# Wireless.net
KiCad netlist of a schematic drawn in Altium Designer
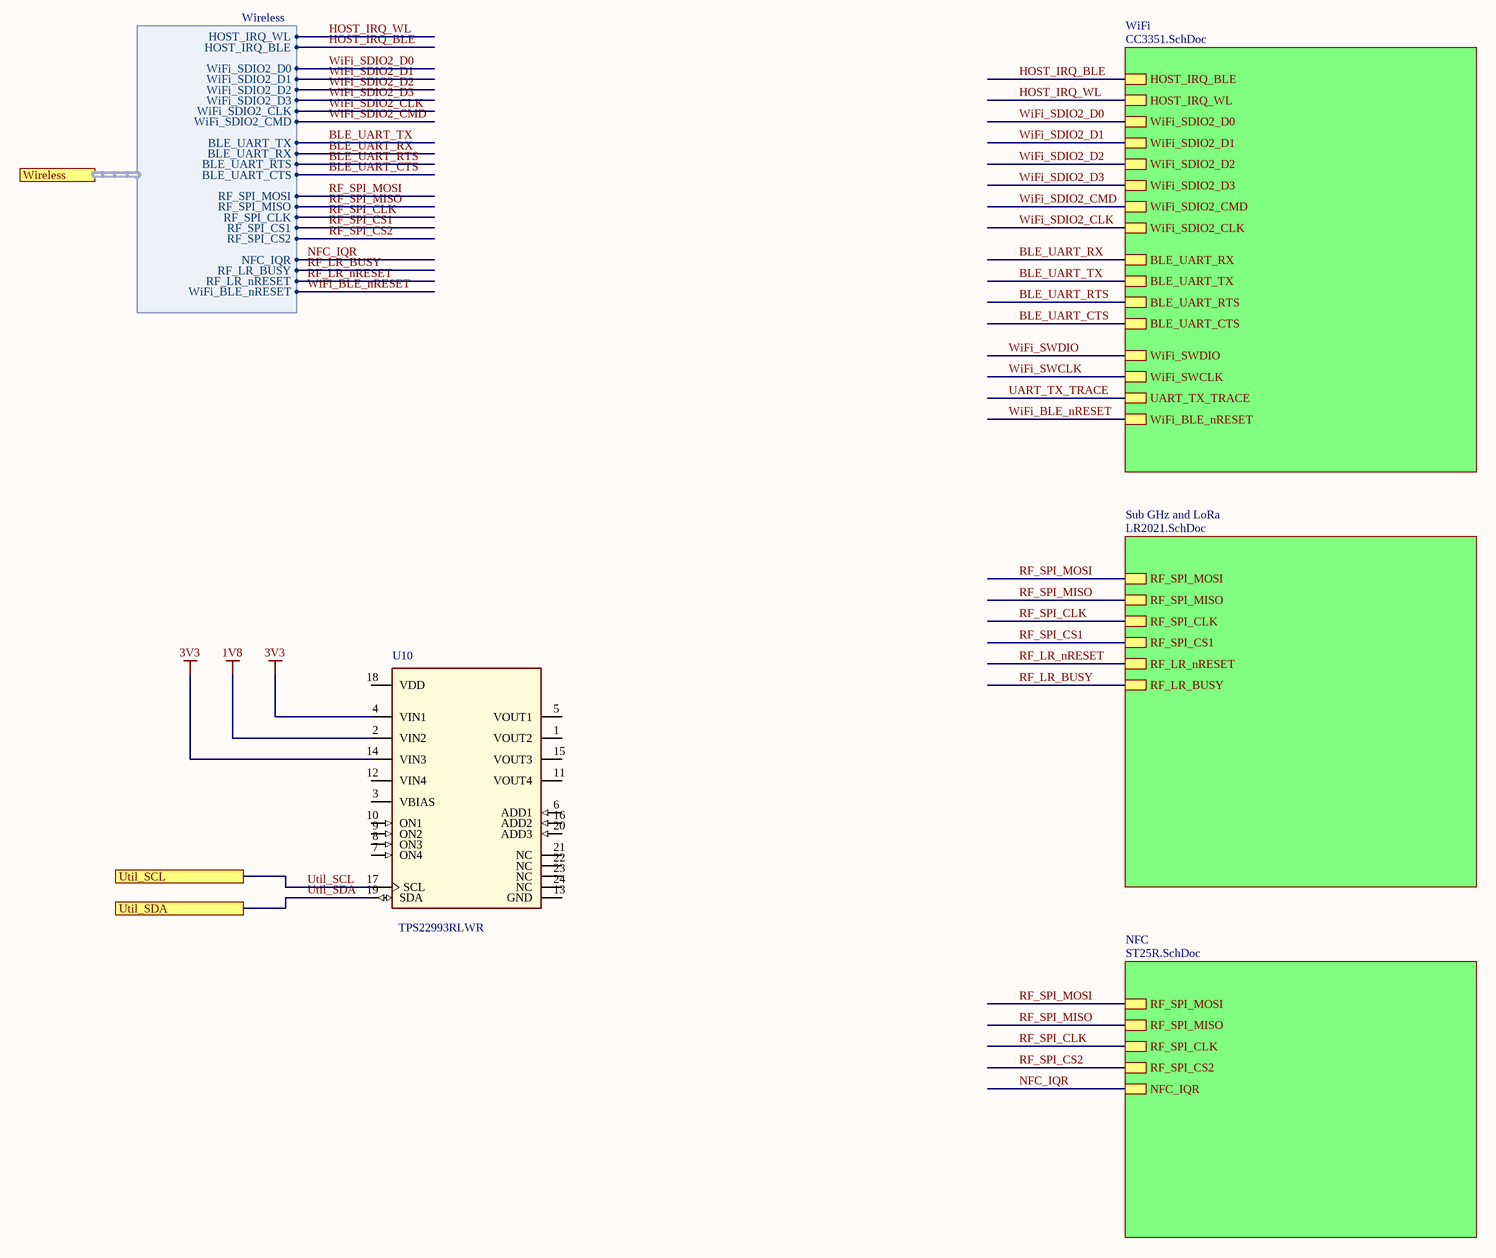
[diagram p0: Wireless.SchDoc]

(export (version "E")
  (design (tool "Eeschema 10.0.6"))
  (components
    (comp (ref "U10")
      (value "TPS22993RLWR")
      (footprint "FP-RLW0020A-MFG")
      (description "IC PWR SWITCH N-CHAN 1:1 20WQFN")
      (libsource (lib "Handheld") (part "TPS22993"))
    )
  )
  (nets
    (net (code "17") (name "/Util_SCL") (class "Default")
      (node (ref "U10") (pin "17") (pinfunction "SCL_17") (pintype "passive"))
    )
    (net (code "18") (name "/Util_SDA") (class "Default")
      (node (ref "U10") (pin "19") (pinfunction "SDA_19") (pintype "bidirectional"))
    )
    (net (code "29") (name "1V8") (class "Default")
      (node (ref "U10") (pin "2") (pinfunction "VIN2_2") (pintype "power_in"))
    )
    (net (code "30") (name "3V3") (class "Default")
      (node (ref "U10") (pin "14") (pinfunction "VIN3_14") (pintype "power_in"))
      (node (ref "U10") (pin "4") (pinfunction "VIN1_4") (pintype "power_in"))
    )
    (net (code "31") (name "unconnected-(U10-ADD1-Pad6)") (class "Default")
      (node (ref "U10") (pin "6") (pinfunction "ADD1_6") (pintype "input"))
    )
    (net (code "32") (name "unconnected-(U10-ADD2-Pad16)") (class "Default")
      (node (ref "U10") (pin "16") (pinfunction "ADD2_16") (pintype "input"))
    )
    (net (code "33") (name "unconnected-(U10-ADD3-Pad20)") (class "Default")
      (node (ref "U10") (pin "20") (pinfunction "ADD3_20") (pintype "input"))
    )
    (net (code "34") (name "unconnected-(U10-GND-Pad13)") (class "Default")
      (node (ref "U10") (pin "13") (pinfunction "GND_13") (pintype "power_in"))
    )
    (net (code "35") (name "unconnected-(U10-NC-Pad21)") (class "Default")
      (node (ref "U10") (pin "21") (pinfunction "NC_21") (pintype "passive"))
    )
    (net (code "36") (name "unconnected-(U10-NC-Pad22)") (class "Default")
      (node (ref "U10") (pin "22") (pinfunction "NC_22") (pintype "passive"))
    )
    (net (code "37") (name "unconnected-(U10-NC-Pad23)") (class "Default")
      (node (ref "U10") (pin "23") (pinfunction "NC_23") (pintype "passive"))
    )
    (net (code "38") (name "unconnected-(U10-NC-Pad24)") (class "Default")
      (node (ref "U10") (pin "24") (pinfunction "NC_24") (pintype "passive"))
    )
    (net (code "39") (name "unconnected-(U10-ON1-Pad10)") (class "Default")
      (node (ref "U10") (pin "10") (pinfunction "ON1_10") (pintype "input"))
    )
    (net (code "40") (name "unconnected-(U10-ON2-Pad9)") (class "Default")
      (node (ref "U10") (pin "9") (pinfunction "ON2_9") (pintype "input"))
    )
    (net (code "41") (name "unconnected-(U10-ON3-Pad8)") (class "Default")
      (node (ref "U10") (pin "8") (pinfunction "ON3_8") (pintype "input"))
    )
    (net (code "42") (name "unconnected-(U10-ON4-Pad7)") (class "Default")
      (node (ref "U10") (pin "7") (pinfunction "ON4_7") (pintype "input"))
    )
    (net (code "43") (name "unconnected-(U10-VBIAS-Pad3)") (class "Default")
      (node (ref "U10") (pin "3") (pinfunction "VBIAS_3") (pintype "power_in"))
    )
    (net (code "44") (name "unconnected-(U10-VDD-Pad18)") (class "Default")
      (node (ref "U10") (pin "18") (pinfunction "VDD_18") (pintype "power_in"))
    )
    (net (code "45") (name "unconnected-(U10-VIN4-Pad12)") (class "Default")
      (node (ref "U10") (pin "12") (pinfunction "VIN4_12") (pintype "power_in"))
    )
    (net (code "46") (name "unconnected-(U10-VOUT1-Pad5)") (class "Default")
      (node (ref "U10") (pin "5") (pinfunction "VOUT1_5") (pintype "passive"))
    )
    (net (code "47") (name "unconnected-(U10-VOUT2-Pad1)") (class "Default")
      (node (ref "U10") (pin "1") (pinfunction "VOUT2_1") (pintype "passive"))
    )
    (net (code "48") (name "unconnected-(U10-VOUT3-Pad15)") (class "Default")
      (node (ref "U10") (pin "15") (pinfunction "VOUT3_15") (pintype "passive"))
    )
    (net (code "49") (name "unconnected-(U10-VOUT4-Pad11)") (class "Default")
      (node (ref "U10") (pin "11") (pinfunction "VOUT4_11") (pintype "passive"))
    )
  )
)
